# LCD_KEYb_final_rev02.net
KiCad netlist of a schematic drawn in EAGLE
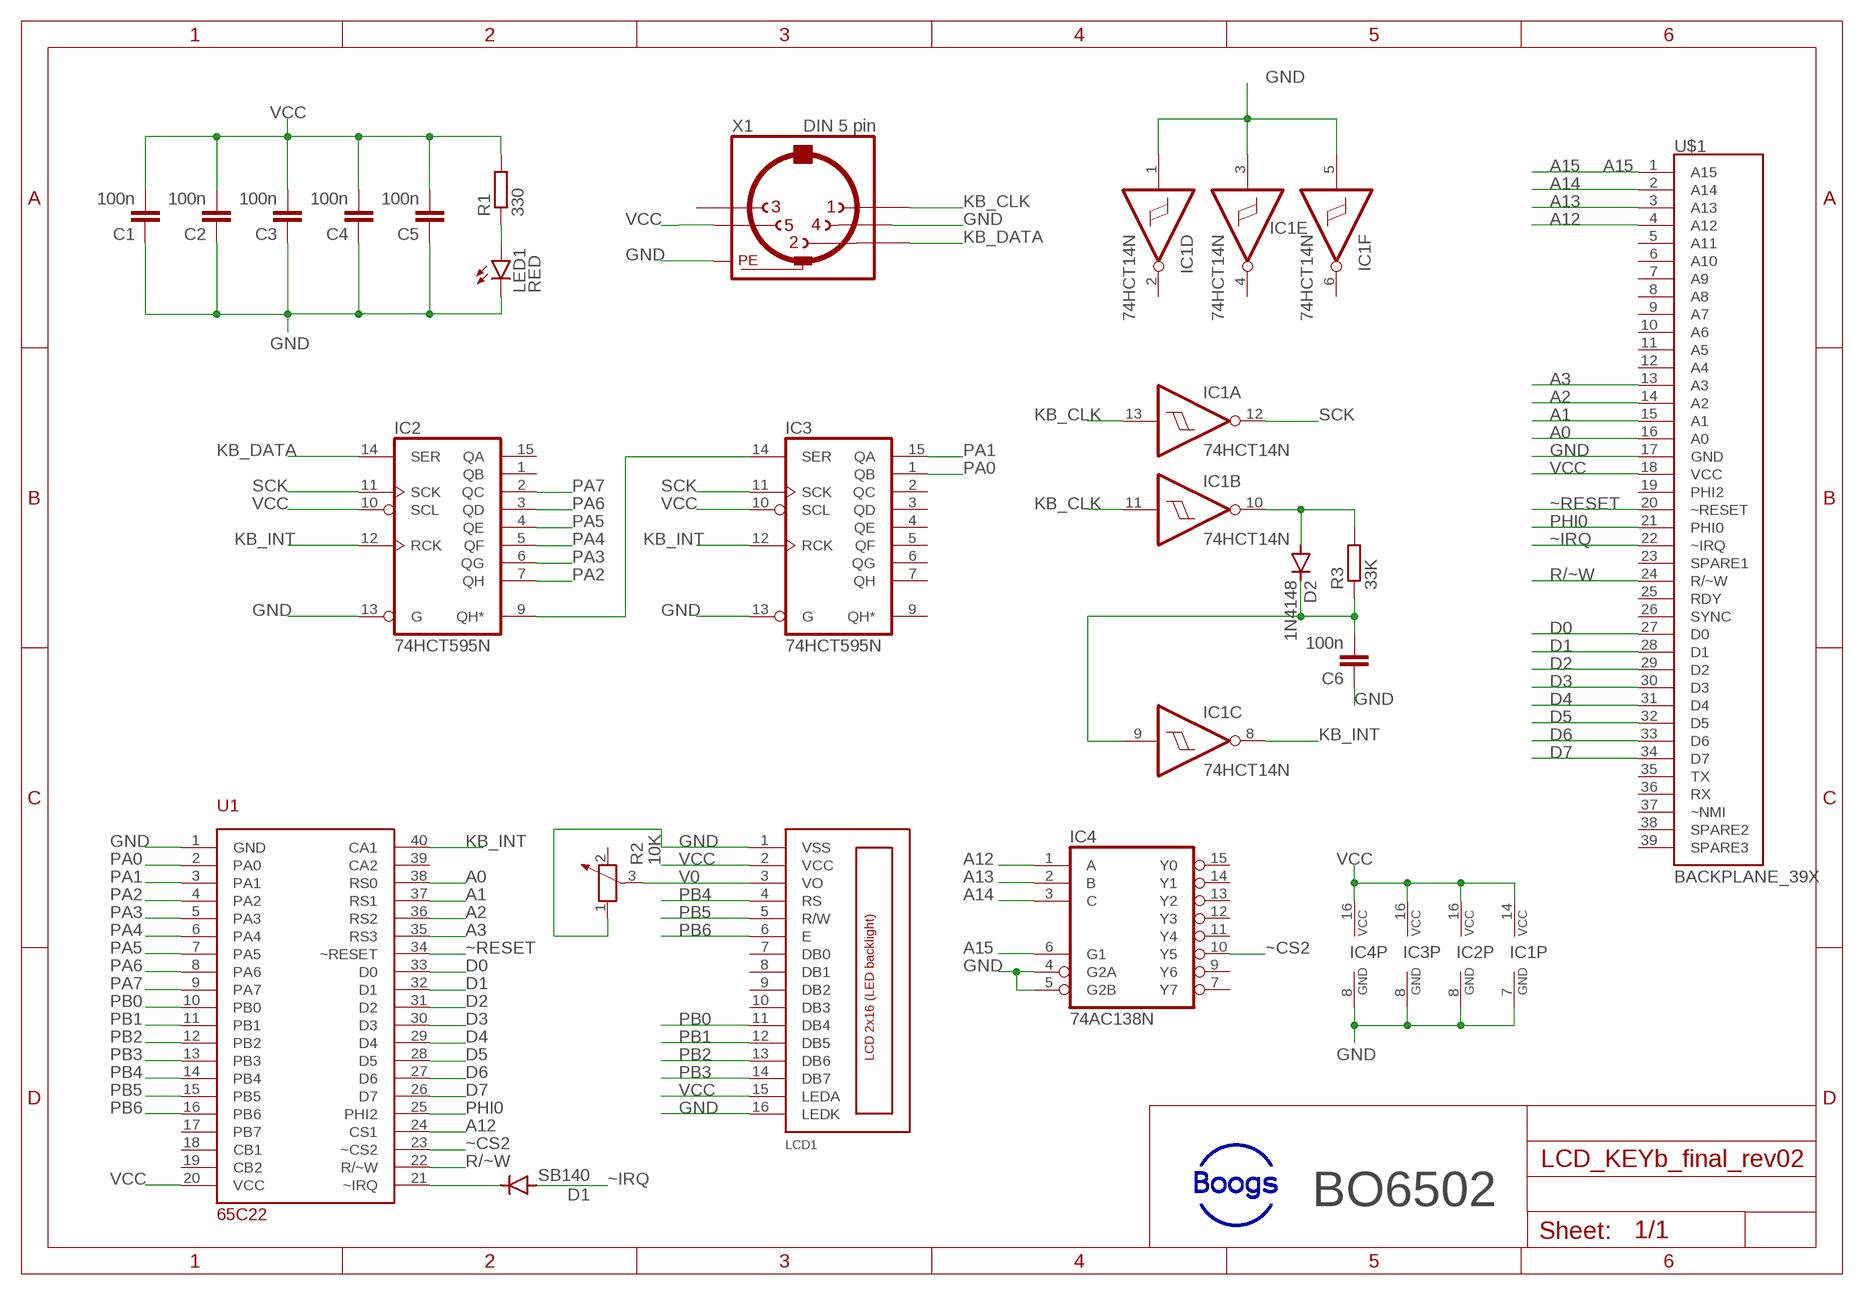
[diagram p0: schematic, sheet 1]

(export (version "E")
  (design (tool "Eeschema 10.0.6"))
  (components
    (comp (ref "C1")
      (value "100n")
      (footprint "eagle-import:C025-025X050")
      (libsource (lib "eagle-import") (part "C-EU025-025X050"))
    )
    (comp (ref "C2")
      (value "100n")
      (footprint "eagle-import:C025-025X050")
      (libsource (lib "eagle-import") (part "C-EU025-025X050"))
    )
    (comp (ref "C3")
      (value "100n")
      (footprint "eagle-import:C025-025X050")
      (libsource (lib "eagle-import") (part "C-EU025-025X050"))
    )
    (comp (ref "C4")
      (value "100n")
      (footprint "eagle-import:C025-025X050")
      (libsource (lib "eagle-import") (part "C-EU025-025X050"))
    )
    (comp (ref "C5")
      (value "100n")
      (footprint "eagle-import:C025-025X050")
      (libsource (lib "eagle-import") (part "C-EU025-025X050"))
    )
    (comp (ref "C6")
      (value "100n")
      (footprint "eagle-import:C025-025X050")
      (libsource (lib "eagle-import") (part "C-EU025-025X050"))
    )
    (comp (ref "D1")
      (value "SB140")
      (footprint "eagle-import:DO41-10")
      (libsource (lib "eagle-import") (part "1N4004"))
    )
    (comp (ref "D2")
      (value "1N4148")
      (footprint "eagle-import:DO35-7")
      (libsource (lib "eagle-import") (part "1N4148DO35-7"))
    )
    (comp (ref "IC1")
      (value "74HCT14N")
      (footprint "eagle-import:DIL14")
      (libsource (lib "eagle-import") (part "7414NHCT"))
    )
    (comp (ref "IC2")
      (value "74HCT595N")
      (footprint "eagle-import:DIL16")
      (libsource (lib "eagle-import") (part "74595NHCT"))
    )
    (comp (ref "IC3")
      (value "74HCT595N")
      (footprint "eagle-import:DIL16")
      (libsource (lib "eagle-import") (part "74595NHCT"))
    )
    (comp (ref "IC4")
      (value "74AC138N")
      (footprint "eagle-import:DIL16")
      (libsource (lib "eagle-import") (part "74138NAC"))
    )
    (comp (ref "LCD1")
      (value "LCD_2X16_SIL")
      (footprint "eagle-import:HY-1602F")
      (libsource (lib "eagle-import") (part "LCD_2X16_SIL"))
    )
    (comp (ref "LED1")
      (value "RED")
      (footprint "eagle-import:LED5MM")
      (libsource (lib "eagle-import") (part "LED5MM"))
    )
    (comp (ref "R1")
      (value "330")
      (footprint "eagle-import:0207_10")
      (libsource (lib "eagle-import") (part "R-EU_0207/10"))
    )
    (comp (ref "R2")
      (value "10K")
      (footprint "eagle-import:PT-10")
      (libsource (lib "eagle-import") (part "POTENTIOMETER_PT-10"))
    )
    (comp (ref "R3")
      (value "33K")
      (footprint "eagle-import:0207_10")
      (libsource (lib "eagle-import") (part "R-EU_0207/10"))
    )
    (comp (ref "U$1")
      (value "BACKPLANE_39X")
      (footprint "eagle-import:BP_39X")
      (fields (field (name "A15") "A15"))
      (libsource (lib "eagle-import") (part "BACKPLANE_39X"))
    )
    (comp (ref "U1")
      (value "65C22")
      (footprint "eagle-import:DIL40")
      (libsource (lib "eagle-import") (part "65C22"))
    )
    (comp (ref "X1")
      (value "DIN 5 pin")
      (footprint "eagle-import:MAB5SH")
      (libsource (lib "eagle-import") (part "MAB5SH"))
    )
  )
  (nets
    (net (code "1") (name "/A0") (class "Default")
      (node (ref "U$1") (pin "16") (pinfunction "A0_16") (pintype "bidirectional"))
      (node (ref "U1") (pin "38") (pinfunction "RS0_38") (pintype "bidirectional"))
    )
    (net (code "2") (name "/A1") (class "Default")
      (node (ref "U$1") (pin "15") (pinfunction "A1_15") (pintype "bidirectional"))
      (node (ref "U1") (pin "37") (pinfunction "RS1_37") (pintype "bidirectional"))
    )
    (net (code "3") (name "/A2") (class "Default")
      (node (ref "U$1") (pin "14") (pinfunction "A2_14") (pintype "bidirectional"))
      (node (ref "U1") (pin "36") (pinfunction "RS2_36") (pintype "bidirectional"))
    )
    (net (code "4") (name "/A3") (class "Default")
      (node (ref "U$1") (pin "13") (pinfunction "A3_13") (pintype "bidirectional"))
      (node (ref "U1") (pin "35") (pinfunction "RS3_35") (pintype "bidirectional"))
    )
    (net (code "5") (name "/A12") (class "Default")
      (node (ref "IC4") (pin "1") (pinfunction "A_1") (pintype "input"))
      (node (ref "U$1") (pin "4") (pinfunction "A12_4") (pintype "bidirectional"))
      (node (ref "U1") (pin "24") (pinfunction "CS1_24") (pintype "bidirectional"))
    )
    (net (code "6") (name "/A13") (class "Default")
      (node (ref "IC4") (pin "2") (pinfunction "B_2") (pintype "input"))
      (node (ref "U$1") (pin "3") (pinfunction "A13_3") (pintype "bidirectional"))
    )
    (net (code "7") (name "/A14") (class "Default")
      (node (ref "IC4") (pin "3") (pinfunction "C_3") (pintype "input"))
      (node (ref "U$1") (pin "2") (pinfunction "A14_2") (pintype "bidirectional"))
    )
    (net (code "8") (name "/A15") (class "Default")
      (node (ref "IC4") (pin "6") (pinfunction "G1_6") (pintype "input"))
      (node (ref "U$1") (pin "1") (pinfunction "A15_1") (pintype "bidirectional"))
    )
    (net (code "9") (name "/D0") (class "Default")
      (node (ref "U$1") (pin "27") (pinfunction "D0_27") (pintype "bidirectional"))
      (node (ref "U1") (pin "33") (pinfunction "D0_33") (pintype "bidirectional"))
    )
    (net (code "10") (name "/D1") (class "Default")
      (node (ref "U$1") (pin "28") (pinfunction "D1_28") (pintype "bidirectional"))
      (node (ref "U1") (pin "32") (pinfunction "D1_32") (pintype "bidirectional"))
    )
    (net (code "11") (name "/D2") (class "Default")
      (node (ref "U$1") (pin "29") (pinfunction "D2_29") (pintype "bidirectional"))
      (node (ref "U1") (pin "31") (pinfunction "D2_31") (pintype "bidirectional"))
    )
    (net (code "12") (name "/D3") (class "Default")
      (node (ref "U$1") (pin "30") (pinfunction "D3_30") (pintype "bidirectional"))
      (node (ref "U1") (pin "30") (pinfunction "D3_30") (pintype "bidirectional"))
    )
    (net (code "13") (name "/D4") (class "Default")
      (node (ref "U$1") (pin "31") (pinfunction "D4_31") (pintype "bidirectional"))
      (node (ref "U1") (pin "29") (pinfunction "D4_29") (pintype "bidirectional"))
    )
    (net (code "14") (name "/D5") (class "Default")
      (node (ref "U$1") (pin "32") (pinfunction "D5_32") (pintype "bidirectional"))
      (node (ref "U1") (pin "28") (pinfunction "D5_28") (pintype "bidirectional"))
    )
    (net (code "15") (name "/D6") (class "Default")
      (node (ref "U$1") (pin "33") (pinfunction "D6_33") (pintype "bidirectional"))
      (node (ref "U1") (pin "27") (pinfunction "D6_27") (pintype "bidirectional"))
    )
    (net (code "16") (name "/D7") (class "Default")
      (node (ref "U$1") (pin "34") (pinfunction "D7_34") (pintype "bidirectional"))
      (node (ref "U1") (pin "26") (pinfunction "D7_26") (pintype "bidirectional"))
    )
    (net (code "17") (name "/GND") (class "Default")
      (node (ref "C1") (pin "1") (pinfunction "1_1") (pintype "passive"))
      (node (ref "C2") (pin "1") (pinfunction "1_1") (pintype "passive"))
      (node (ref "C3") (pin "1") (pinfunction "1_1") (pintype "passive"))
      (node (ref "C4") (pin "1") (pinfunction "1_1") (pintype "passive"))
      (node (ref "C5") (pin "1") (pinfunction "1_1") (pintype "passive"))
      (node (ref "C6") (pin "1") (pinfunction "1_1") (pintype "passive"))
      (node (ref "IC1") (pin "1") (pinfunction "I_1") (pintype "input"))
      (node (ref "IC1") (pin "3") (pinfunction "I_3") (pintype "input"))
      (node (ref "IC1") (pin "5") (pinfunction "I_5") (pintype "input"))
      (node (ref "IC1") (pin "7") (pinfunction "GND_7") (pintype "power_in"))
      (node (ref "IC2") (pin "13") (pinfunction "G_13") (pintype "input"))
      (node (ref "IC2") (pin "8") (pinfunction "GND_8") (pintype "power_in"))
      (node (ref "IC3") (pin "13") (pinfunction "G_13") (pintype "input"))
      (node (ref "IC3") (pin "8") (pinfunction "GND_8") (pintype "power_in"))
      (node (ref "IC4") (pin "4") (pinfunction "G2A_4") (pintype "input"))
      (node (ref "IC4") (pin "5") (pinfunction "G2B_5") (pintype "input"))
      (node (ref "IC4") (pin "8") (pinfunction "GND_8") (pintype "power_in"))
      (node (ref "LCD1") (pin "1") (pinfunction "VSS_1") (pintype "power_in"))
      (node (ref "LCD1") (pin "16") (pinfunction "LEDK_16") (pintype "passive"))
      (node (ref "LED1") (pin "K") (pinfunction "C_K") (pintype "passive"))
      (node (ref "R2") (pin "1") (pinfunction "1_1") (pintype "passive"))
      (node (ref "U$1") (pin "17") (pinfunction "GND_17") (pintype "bidirectional"))
      (node (ref "U1") (pin "1") (pinfunction "GND_1") (pintype "bidirectional"))
      (node (ref "X1") (pin "4") (pinfunction "4_4") (pintype "passive"))
      (node (ref "X1") (pin "PE") (pinfunction "PE_PE") (pintype "power_in"))
      (node (ref "X1") (pin "PE@") (pinfunction "PE_PE@") (pintype "power_in"))
    )
    (net (code "18") (name "/KB_CLK") (class "Default")
      (node (ref "IC1") (pin "11") (pinfunction "I_11") (pintype "input"))
      (node (ref "IC1") (pin "13") (pinfunction "I_13") (pintype "input"))
      (node (ref "X1") (pin "1") (pinfunction "1_1") (pintype "passive"))
    )
    (net (code "19") (name "/KB_DATA") (class "Default")
      (node (ref "IC2") (pin "14") (pinfunction "SER_14") (pintype "input"))
      (node (ref "X1") (pin "2") (pinfunction "2_2") (pintype "passive"))
    )
    (net (code "20") (name "/KB_INT") (class "Default")
      (node (ref "IC1") (pin "8") (pinfunction "O_8") (pintype "output"))
      (node (ref "IC2") (pin "12") (pinfunction "RCK_12") (pintype "input"))
      (node (ref "IC3") (pin "12") (pinfunction "RCK_12") (pintype "input"))
      (node (ref "U1") (pin "40") (pinfunction "CA1_40") (pintype "bidirectional"))
    )
    (net (code "21") (name "/PA0") (class "Default")
      (node (ref "IC3") (pin "1") (pinfunction "QB_1") (pintype "tri_state"))
      (node (ref "U1") (pin "2") (pinfunction "PA0_2") (pintype "bidirectional"))
    )
    (net (code "22") (name "/PA1") (class "Default")
      (node (ref "IC3") (pin "15") (pinfunction "QA_15") (pintype "tri_state"))
      (node (ref "U1") (pin "3") (pinfunction "PA1_3") (pintype "bidirectional"))
    )
    (net (code "23") (name "/PA2") (class "Default")
      (node (ref "IC2") (pin "7") (pinfunction "QH_7") (pintype "tri_state"))
      (node (ref "U1") (pin "4") (pinfunction "PA2_4") (pintype "bidirectional"))
    )
    (net (code "24") (name "/PA3") (class "Default")
      (node (ref "IC2") (pin "6") (pinfunction "QG_6") (pintype "tri_state"))
      (node (ref "U1") (pin "5") (pinfunction "PA3_5") (pintype "bidirectional"))
    )
    (net (code "25") (name "/PA4") (class "Default")
      (node (ref "IC2") (pin "5") (pinfunction "QF_5") (pintype "tri_state"))
      (node (ref "U1") (pin "6") (pinfunction "PA4_6") (pintype "bidirectional"))
    )
    (net (code "26") (name "/PA5") (class "Default")
      (node (ref "IC2") (pin "4") (pinfunction "QE_4") (pintype "tri_state"))
      (node (ref "U1") (pin "7") (pinfunction "PA5_7") (pintype "bidirectional"))
    )
    (net (code "27") (name "/PA6") (class "Default")
      (node (ref "IC2") (pin "3") (pinfunction "QD_3") (pintype "tri_state"))
      (node (ref "U1") (pin "8") (pinfunction "PA6_8") (pintype "bidirectional"))
    )
    (net (code "28") (name "/PA7") (class "Default")
      (node (ref "IC2") (pin "2") (pinfunction "QC_2") (pintype "tri_state"))
      (node (ref "U1") (pin "9") (pinfunction "PA7_9") (pintype "bidirectional"))
    )
    (net (code "29") (name "/PB0") (class "Default")
      (node (ref "LCD1") (pin "11") (pinfunction "DB4_11") (pintype "bidirectional"))
      (node (ref "U1") (pin "10") (pinfunction "PB0_10") (pintype "bidirectional"))
    )
    (net (code "30") (name "/PB1") (class "Default")
      (node (ref "LCD1") (pin "12") (pinfunction "DB5_12") (pintype "bidirectional"))
      (node (ref "U1") (pin "11") (pinfunction "PB1_11") (pintype "bidirectional"))
    )
    (net (code "31") (name "/PB2") (class "Default")
      (node (ref "LCD1") (pin "13") (pinfunction "DB6_13") (pintype "bidirectional"))
      (node (ref "U1") (pin "12") (pinfunction "PB2_12") (pintype "bidirectional"))
    )
    (net (code "32") (name "/PB3") (class "Default")
      (node (ref "LCD1") (pin "14") (pinfunction "DB7_14") (pintype "bidirectional"))
      (node (ref "U1") (pin "13") (pinfunction "PB3_13") (pintype "bidirectional"))
    )
    (net (code "33") (name "/PB4") (class "Default")
      (node (ref "LCD1") (pin "4") (pinfunction "RS_4") (pintype "input"))
      (node (ref "U1") (pin "14") (pinfunction "PB4_14") (pintype "bidirectional"))
    )
    (net (code "34") (name "/PB5") (class "Default")
      (node (ref "LCD1") (pin "5") (pinfunction "R/W_5") (pintype "input"))
      (node (ref "U1") (pin "15") (pinfunction "PB5_15") (pintype "bidirectional"))
    )
    (net (code "35") (name "/PB6") (class "Default")
      (node (ref "LCD1") (pin "6") (pinfunction "E_6") (pintype "input"))
      (node (ref "U1") (pin "16") (pinfunction "PB6_16") (pintype "bidirectional"))
    )
    (net (code "36") (name "/PHI0") (class "Default")
      (node (ref "U$1") (pin "21") (pinfunction "PHI0_21") (pintype "bidirectional"))
      (node (ref "U1") (pin "25") (pinfunction "PHI2_25") (pintype "bidirectional"))
    )
    (net (code "37") (name "/R{slash}~{W}") (class "Default")
      (node (ref "U$1") (pin "24") (pinfunction "R/~{W}_24") (pintype "bidirectional"))
      (node (ref "U1") (pin "22") (pinfunction "R/~{W}_22") (pintype "bidirectional"))
    )
    (net (code "38") (name "/SCK") (class "Default")
      (node (ref "IC1") (pin "12") (pinfunction "O_12") (pintype "output"))
      (node (ref "IC2") (pin "11") (pinfunction "SCK_11") (pintype "input"))
      (node (ref "IC3") (pin "11") (pinfunction "SCK_11") (pintype "input"))
    )
    (net (code "39") (name "/V0") (class "Default")
      (node (ref "LCD1") (pin "3") (pinfunction "VO_3") (pintype "input"))
      (node (ref "R2") (pin "3") (pinfunction "3_3") (pintype "passive"))
    )
    (net (code "40") (name "/VCC") (class "Default")
      (node (ref "C1") (pin "2") (pinfunction "2_2") (pintype "passive"))
      (node (ref "C2") (pin "2") (pinfunction "2_2") (pintype "passive"))
      (node (ref "C3") (pin "2") (pinfunction "2_2") (pintype "passive"))
      (node (ref "C4") (pin "2") (pinfunction "2_2") (pintype "passive"))
      (node (ref "C5") (pin "2") (pinfunction "2_2") (pintype "passive"))
      (node (ref "IC1") (pin "14") (pinfunction "VCC_14") (pintype "power_in"))
      (node (ref "IC2") (pin "10") (pinfunction "SCL_10") (pintype "input"))
      (node (ref "IC2") (pin "16") (pinfunction "VCC_16") (pintype "power_in"))
      (node (ref "IC3") (pin "10") (pinfunction "SCL_10") (pintype "input"))
      (node (ref "IC3") (pin "16") (pinfunction "VCC_16") (pintype "power_in"))
      (node (ref "IC4") (pin "16") (pinfunction "VCC_16") (pintype "power_in"))
      (node (ref "LCD1") (pin "15") (pinfunction "LEDA_15") (pintype "passive"))
      (node (ref "LCD1") (pin "2") (pinfunction "VCC_2") (pintype "power_in"))
      (node (ref "R1") (pin "2") (pinfunction "2_2") (pintype "passive"))
      (node (ref "U$1") (pin "18") (pinfunction "VCC_18") (pintype "bidirectional"))
      (node (ref "U1") (pin "20") (pinfunction "VCC_20") (pintype "bidirectional"))
      (node (ref "X1") (pin "5") (pinfunction "5_5") (pintype "passive"))
    )
    (net (code "41") (name "/~{CS2}") (class "Default")
      (node (ref "IC4") (pin "10") (pinfunction "Y5_10") (pintype "output"))
      (node (ref "U1") (pin "23") (pinfunction "~{CS2}_23") (pintype "bidirectional"))
    )
    (net (code "42") (name "/~{IRQ}") (class "Default")
      (node (ref "D1") (pin "A") (pinfunction "A_A") (pintype "passive"))
      (node (ref "U$1") (pin "22") (pinfunction "~{IRQ}_22") (pintype "bidirectional"))
    )
    (net (code "43") (name "/~{RESET}") (class "Default")
      (node (ref "U$1") (pin "20") (pinfunction "~{RESET}_20") (pintype "bidirectional"))
      (node (ref "U1") (pin "34") (pinfunction "~{RESET}_34") (pintype "bidirectional"))
    )
    (net (code "44") (name "Net-(IC1B-O)") (class "Default")
      (node (ref "D2") (pin "A") (pinfunction "A_A") (pintype "passive"))
      (node (ref "IC1") (pin "10") (pinfunction "O_10") (pintype "output"))
      (node (ref "R3") (pin "2") (pinfunction "2_2") (pintype "passive"))
    )
    (net (code "45") (name "Net-(IC1C-I)") (class "Default")
      (node (ref "C6") (pin "2") (pinfunction "2_2") (pintype "passive"))
      (node (ref "D2") (pin "C") (pinfunction "C_C") (pintype "passive"))
      (node (ref "IC1") (pin "9") (pinfunction "I_9") (pintype "input"))
      (node (ref "R3") (pin "1") (pinfunction "1_1") (pintype "passive"))
    )
    (net (code "46") (name "Net-(IC2A-QH*)") (class "Default")
      (node (ref "IC2") (pin "9") (pinfunction "QH*_9") (pintype "tri_state"))
      (node (ref "IC3") (pin "14") (pinfunction "SER_14") (pintype "input"))
    )
    (net (code "47") (name "Net-(LED1-PadA)") (class "Default")
      (node (ref "LED1") (pin "A") (pinfunction "A_A") (pintype "passive"))
      (node (ref "R1") (pin "1") (pinfunction "1_1") (pintype "passive"))
    )
    (net (code "48") (name "Net-(U1-~{IRQ})") (class "Default")
      (node (ref "D1") (pin "C") (pinfunction "C_C") (pintype "passive"))
      (node (ref "U1") (pin "21") (pinfunction "~{IRQ}_21") (pintype "bidirectional"))
    )
    (net (code "49") (name "unconnected-(IC1D-O-Pad2)") (class "Default")
      (node (ref "IC1") (pin "2") (pinfunction "O_2") (pintype "output"))
    )
    (net (code "50") (name "unconnected-(IC1E-O-Pad4)") (class "Default")
      (node (ref "IC1") (pin "4") (pinfunction "O_4") (pintype "output"))
    )
    (net (code "51") (name "unconnected-(IC1F-O-Pad6)") (class "Default")
      (node (ref "IC1") (pin "6") (pinfunction "O_6") (pintype "output"))
    )
    (net (code "52") (name "unconnected-(IC2A-QA-Pad15)") (class "Default")
      (node (ref "IC2") (pin "15") (pinfunction "QA_15") (pintype "tri_state"))
    )
    (net (code "53") (name "unconnected-(IC2A-QB-Pad1)") (class "Default")
      (node (ref "IC2") (pin "1") (pinfunction "QB_1") (pintype "tri_state"))
    )
    (net (code "54") (name "unconnected-(IC3A-QC-Pad2)") (class "Default")
      (node (ref "IC3") (pin "2") (pinfunction "QC_2") (pintype "tri_state"))
    )
    (net (code "55") (name "unconnected-(IC3A-QD-Pad3)") (class "Default")
      (node (ref "IC3") (pin "3") (pinfunction "QD_3") (pintype "tri_state"))
    )
    (net (code "56") (name "unconnected-(IC3A-QE-Pad4)") (class "Default")
      (node (ref "IC3") (pin "4") (pinfunction "QE_4") (pintype "tri_state"))
    )
    (net (code "57") (name "unconnected-(IC3A-QF-Pad5)") (class "Default")
      (node (ref "IC3") (pin "5") (pinfunction "QF_5") (pintype "tri_state"))
    )
    (net (code "58") (name "unconnected-(IC3A-QG-Pad6)") (class "Default")
      (node (ref "IC3") (pin "6") (pinfunction "QG_6") (pintype "tri_state"))
    )
    (net (code "59") (name "unconnected-(IC3A-QH*-Pad9)") (class "Default")
      (node (ref "IC3") (pin "9") (pinfunction "QH*_9") (pintype "tri_state"))
    )
    (net (code "60") (name "unconnected-(IC3A-QH-Pad7)") (class "Default")
      (node (ref "IC3") (pin "7") (pinfunction "QH_7") (pintype "tri_state"))
    )
    (net (code "61") (name "unconnected-(IC4A-Y0-Pad15)") (class "Default")
      (node (ref "IC4") (pin "15") (pinfunction "Y0_15") (pintype "output"))
    )
    (net (code "62") (name "unconnected-(IC4A-Y1-Pad14)") (class "Default")
      (node (ref "IC4") (pin "14") (pinfunction "Y1_14") (pintype "output"))
    )
    (net (code "63") (name "unconnected-(IC4A-Y2-Pad13)") (class "Default")
      (node (ref "IC4") (pin "13") (pinfunction "Y2_13") (pintype "output"))
    )
    (net (code "64") (name "unconnected-(IC4A-Y3-Pad12)") (class "Default")
      (node (ref "IC4") (pin "12") (pinfunction "Y3_12") (pintype "output"))
    )
    (net (code "65") (name "unconnected-(IC4A-Y4-Pad11)") (class "Default")
      (node (ref "IC4") (pin "11") (pinfunction "Y4_11") (pintype "output"))
    )
    (net (code "66") (name "unconnected-(IC4A-Y6-Pad9)") (class "Default")
      (node (ref "IC4") (pin "9") (pinfunction "Y6_9") (pintype "output"))
    )
    (net (code "67") (name "unconnected-(IC4A-Y7-Pad7)") (class "Default")
      (node (ref "IC4") (pin "7") (pinfunction "Y7_7") (pintype "output"))
    )
    (net (code "68") (name "unconnected-(LCD1-DB0-Pad7)") (class "Default")
      (node (ref "LCD1") (pin "7") (pinfunction "DB0_7") (pintype "bidirectional"))
    )
    (net (code "69") (name "unconnected-(LCD1-DB1-Pad8)") (class "Default")
      (node (ref "LCD1") (pin "8") (pinfunction "DB1_8") (pintype "bidirectional"))
    )
    (net (code "70") (name "unconnected-(LCD1-DB2-Pad9)") (class "Default")
      (node (ref "LCD1") (pin "9") (pinfunction "DB2_9") (pintype "bidirectional"))
    )
    (net (code "71") (name "unconnected-(LCD1-DB3-Pad10)") (class "Default")
      (node (ref "LCD1") (pin "10") (pinfunction "DB3_10") (pintype "bidirectional"))
    )
    (net (code "72") (name "unconnected-(R2-Pad2)") (class "Default")
      (node (ref "R2") (pin "2") (pinfunction "2_2") (pintype "passive"))
    )
    (net (code "73") (name "unconnected-(U$1-A4-Pad12)") (class "Default")
      (node (ref "U$1") (pin "12") (pinfunction "A4_12") (pintype "bidirectional"))
    )
    (net (code "74") (name "unconnected-(U$1-A5-Pad11)") (class "Default")
      (node (ref "U$1") (pin "11") (pinfunction "A5_11") (pintype "bidirectional"))
    )
    (net (code "75") (name "unconnected-(U$1-A6-Pad10)") (class "Default")
      (node (ref "U$1") (pin "10") (pinfunction "A6_10") (pintype "bidirectional"))
    )
    (net (code "76") (name "unconnected-(U$1-A7-Pad9)") (class "Default")
      (node (ref "U$1") (pin "9") (pinfunction "A7_9") (pintype "bidirectional"))
    )
    (net (code "77") (name "unconnected-(U$1-A8-Pad8)") (class "Default")
      (node (ref "U$1") (pin "8") (pinfunction "A8_8") (pintype "bidirectional"))
    )
    (net (code "78") (name "unconnected-(U$1-A9-Pad7)") (class "Default")
      (node (ref "U$1") (pin "7") (pinfunction "A9_7") (pintype "bidirectional"))
    )
    (net (code "79") (name "unconnected-(U$1-A10-Pad6)") (class "Default")
      (node (ref "U$1") (pin "6") (pinfunction "A10_6") (pintype "bidirectional"))
    )
    (net (code "80") (name "unconnected-(U$1-A11-Pad5)") (class "Default")
      (node (ref "U$1") (pin "5") (pinfunction "A11_5") (pintype "bidirectional"))
    )
    (net (code "81") (name "unconnected-(U$1-PHI2-Pad19)") (class "Default")
      (node (ref "U$1") (pin "19") (pinfunction "PHI2_19") (pintype "bidirectional"))
    )
    (net (code "82") (name "unconnected-(U$1-RDY-Pad25)") (class "Default")
      (node (ref "U$1") (pin "25") (pinfunction "RDY_25") (pintype "bidirectional"))
    )
    (net (code "83") (name "unconnected-(U$1-RX-Pad36)") (class "Default")
      (node (ref "U$1") (pin "36") (pinfunction "RX_36") (pintype "bidirectional"))
    )
    (net (code "84") (name "unconnected-(U$1-SPARE1-Pad23)") (class "Default")
      (node (ref "U$1") (pin "23") (pinfunction "SPARE1_23") (pintype "bidirectional"))
    )
    (net (code "85") (name "unconnected-(U$1-SPARE2-Pad38)") (class "Default")
      (node (ref "U$1") (pin "38") (pinfunction "SPARE2_38") (pintype "bidirectional"))
    )
    (net (code "86") (name "unconnected-(U$1-SPARE3-Pad39)") (class "Default")
      (node (ref "U$1") (pin "39") (pinfunction "SPARE3_39") (pintype "bidirectional"))
    )
    (net (code "87") (name "unconnected-(U$1-SYNC-Pad26)") (class "Default")
      (node (ref "U$1") (pin "26") (pinfunction "SYNC_26") (pintype "bidirectional"))
    )
    (net (code "88") (name "unconnected-(U$1-TX-Pad35)") (class "Default")
      (node (ref "U$1") (pin "35") (pinfunction "TX_35") (pintype "bidirectional"))
    )
    (net (code "89") (name "unconnected-(U$1-~{NMI}-Pad37)") (class "Default")
      (node (ref "U$1") (pin "37") (pinfunction "~{NMI}_37") (pintype "bidirectional"))
    )
    (net (code "90") (name "unconnected-(U1-CA2-Pad39)") (class "Default")
      (node (ref "U1") (pin "39") (pinfunction "CA2_39") (pintype "bidirectional"))
    )
    (net (code "91") (name "unconnected-(U1-CB1-Pad18)") (class "Default")
      (node (ref "U1") (pin "18") (pinfunction "CB1_18") (pintype "bidirectional"))
    )
    (net (code "92") (name "unconnected-(U1-CB2-Pad19)") (class "Default")
      (node (ref "U1") (pin "19") (pinfunction "CB2_19") (pintype "bidirectional"))
    )
    (net (code "93") (name "unconnected-(U1-PB7-Pad17)") (class "Default")
      (node (ref "U1") (pin "17") (pinfunction "PB7_17") (pintype "bidirectional"))
    )
    (net (code "94") (name "unconnected-(X1-Pad3)") (class "Default")
      (node (ref "X1") (pin "3") (pinfunction "3_3") (pintype "passive"))
    )
  )
)
